# STM32P48.net
KiCad netlist of a schematic drawn in Altium Designer
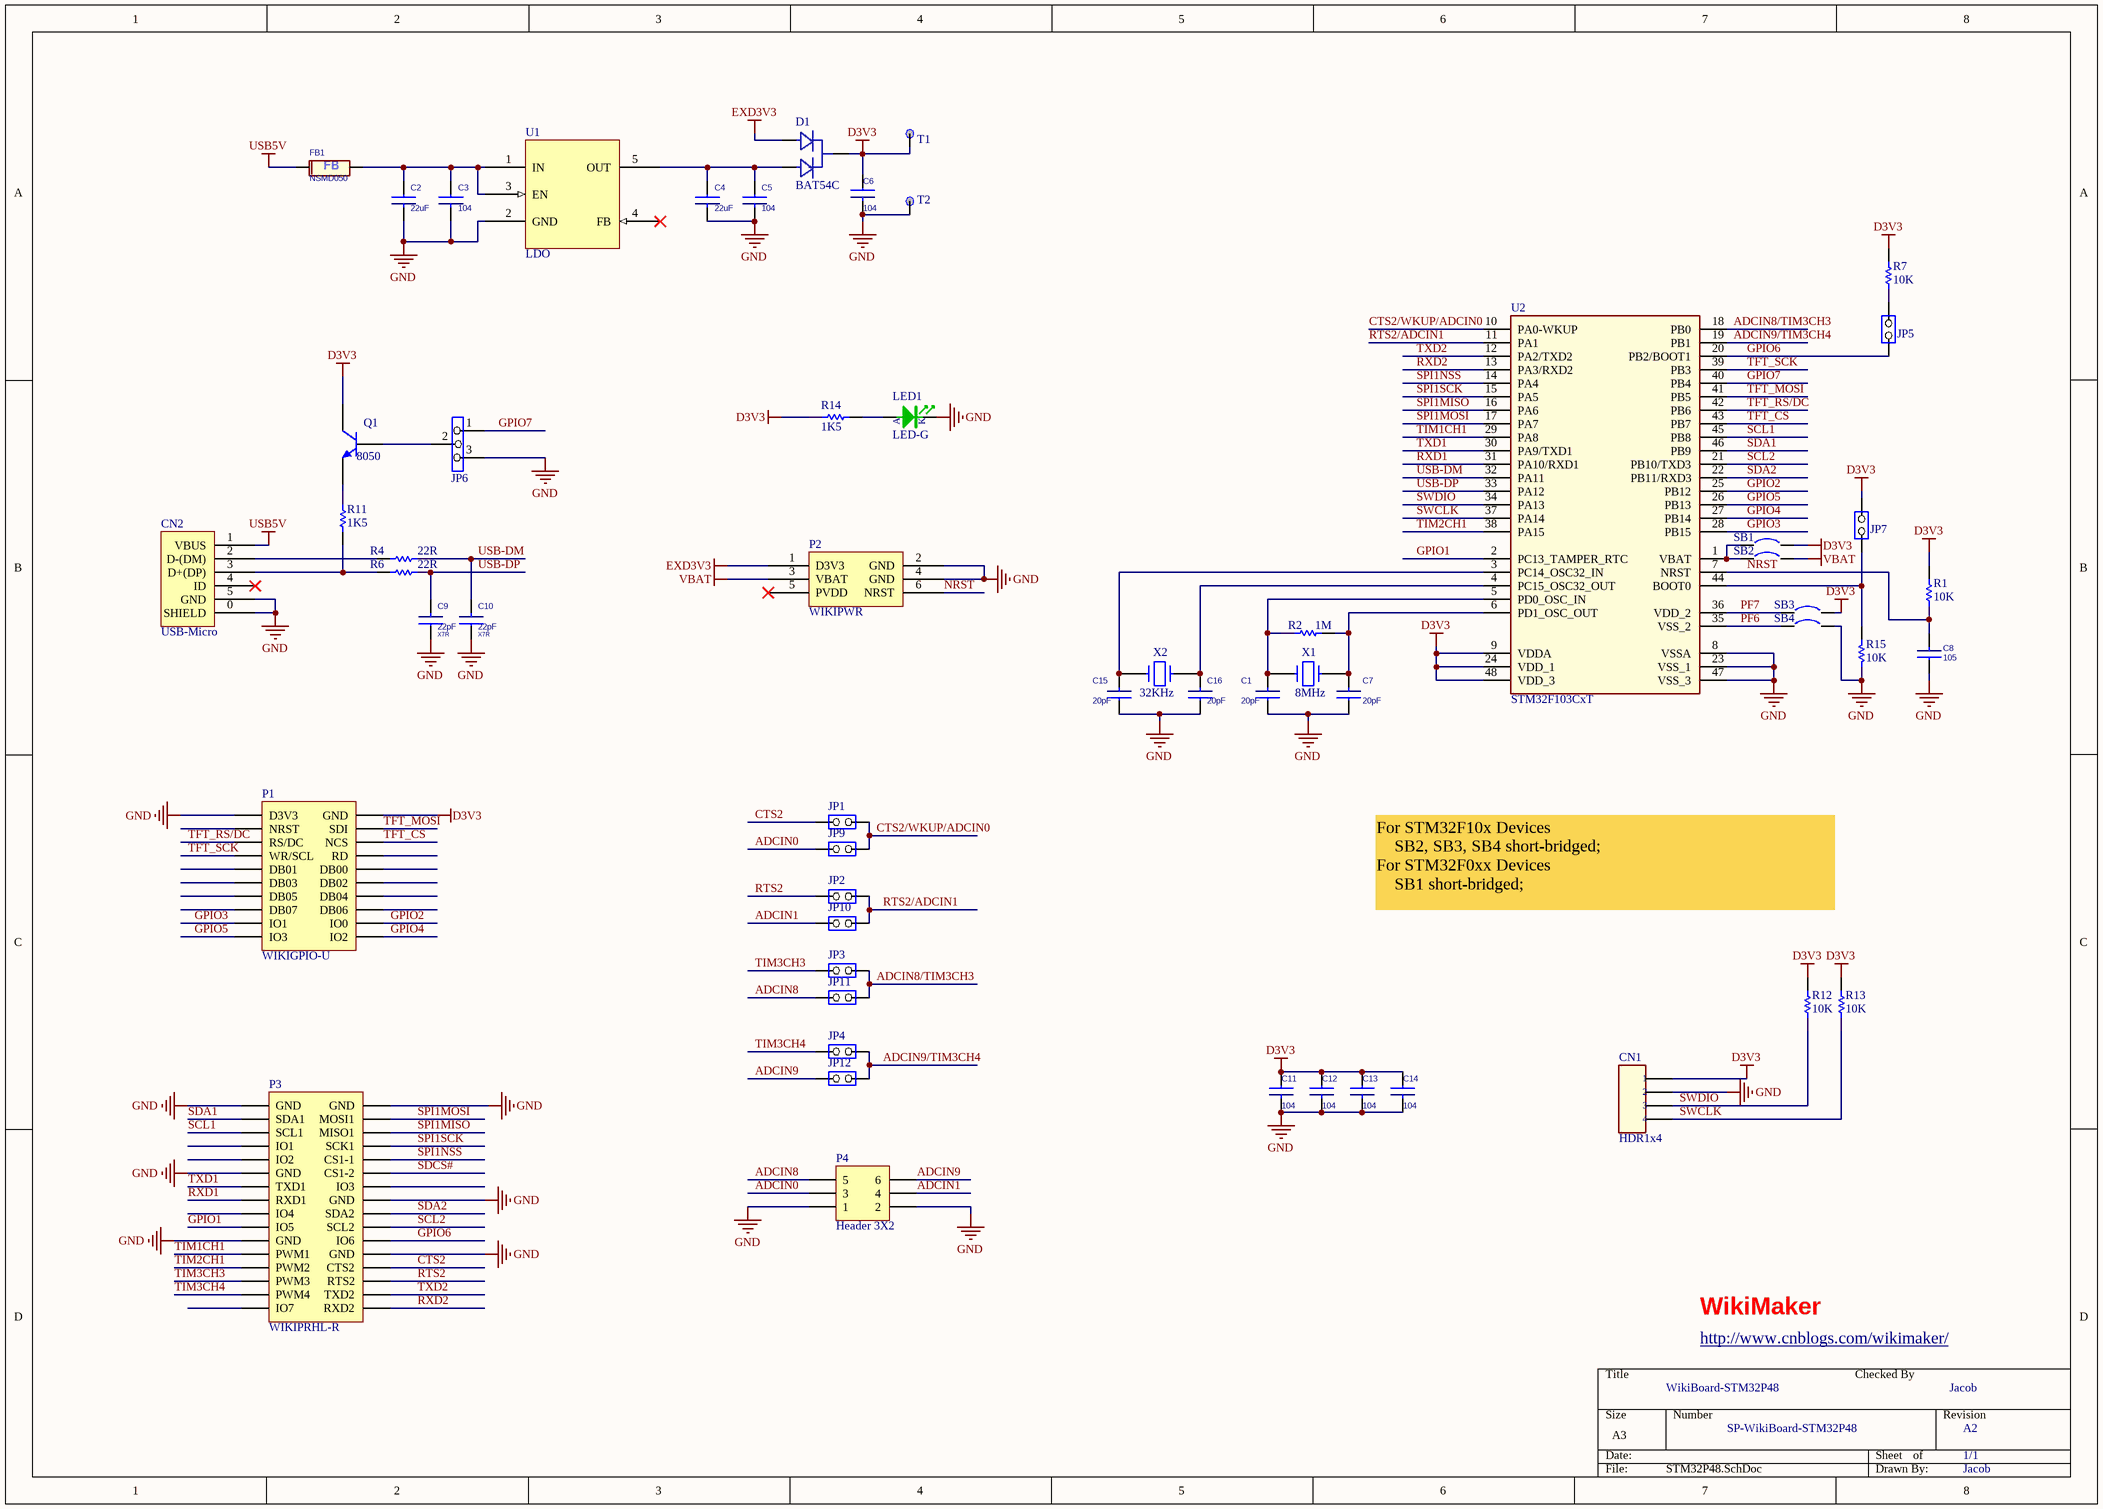
[diagram p0: STM32P48.SchDoc]

(export (version "E")
  (design (tool "Eeschema 10.0.6"))
  (components
    (comp (ref "C1")
      (value "20pF")
      (footprint "C0603")
      (fields (field (name "作者") "符观辉"))
      (libsource (lib "Mylib") (part "CAP"))
    )
    (comp (ref "C2") (value "22uF") (footprint "C0805") (libsource (lib "Mylib") (part "CAP")))
    (comp (ref "C3") (value "104") (footprint "C0603") (libsource (lib "Mylib") (part "CAP")))
    (comp (ref "C4") (value "22uF") (footprint "C0805") (libsource (lib "Mylib") (part "CAP")))
    (comp (ref "C5") (value "104") (footprint "C0603") (libsource (lib "Mylib") (part "CAP")))
    (comp (ref "C6") (value "104") (footprint "C0603") (libsource (lib "Mylib") (part "CAP")))
    (comp (ref "C7")
      (value "20pF")
      (footprint "C0603")
      (fields (field (name "作者") "符观辉"))
      (libsource (lib "Mylib") (part "CAP"))
    )
    (comp (ref "C8")
      (value "105")
      (footprint "C0603")
      (fields (field (name "作者") "符观辉"))
      (libsource (lib "Mylib") (part "CAP"))
    )
    (comp (ref "C9")
      (value "22pF")
      (footprint "C0603")
      (fields (field (name "ALTIUM_UNNAMED_1") "X7R") (field (name "作者") "符观辉"))
      (libsource (lib "Mylib") (part "CAP"))
    )
    (comp (ref "C10")
      (value "22pF")
      (footprint "C0603")
      (fields (field (name "ALTIUM_UNNAMED_1") "X7R") (field (name "作者") "符观辉"))
      (libsource (lib "Mylib") (part "CAP"))
    )
    (comp (ref "C11") (value "104") (footprint "C0603") (libsource (lib "Mylib") (part "CAP")))
    (comp (ref "C12") (value "104") (footprint "C0603") (libsource (lib "Mylib") (part "CAP")))
    (comp (ref "C13") (value "104") (footprint "C0603") (libsource (lib "Mylib") (part "CAP")))
    (comp (ref "C14") (value "104") (footprint "C0603") (libsource (lib "Mylib") (part "CAP")))
    (comp (ref "C15")
      (value "20pF")
      (footprint "C0603")
      (fields (field (name "作者") "符观辉"))
      (libsource (lib "Mylib") (part "CAP"))
    )
    (comp (ref "C16")
      (value "20pF")
      (footprint "C0603")
      (fields (field (name "作者") "符观辉"))
      (libsource (lib "Mylib") (part "CAP"))
    )
    (comp (ref "CN1") (value "HDR1x4") (footprint "HDR1x4") (libsource (lib "Mylib") (part "CON4")))
    (comp (ref "CN2")
      (value "USB-Micro")
      (footprint "USB-MICRO-Lite")
      (libsource (lib "Connector") (part "USB-Micro"))
    )
    (comp (ref "D1")
      (value "BAT54C")
      (footprint "BAT54C")
      (description "DOUBLE SHOTTKEY DIODES")
      (libsource (lib "Misc") (part "BAT54C"))
    )
    (comp (ref "FB1")
      (value "NSMD050")
      (footprint "R1206")
      (description "Ferrite Beads Inductors Impedance:120Ω±25% Rated Current:1500mA DC Resistance:0.095Ω")
      (fields
        (field (name "MANUFACTURER") "muRata")
        (field (name "MANUFACTURER PART NUMBER") "BLM15EG121SN1")
      )
      (libsource (lib "Mylib") (part "FB"))
    )
    (comp (ref "JP1")
      (value "Jumper2-2")
      (footprint "HDR1X2/2.00MM")
      (description "Jumper2")
      (libsource (lib "Misc") (part "Jumper2-2"))
    )
    (comp (ref "JP2")
      (value "Jumper2-2")
      (footprint "HDR1X2/2.00MM")
      (description "Jumper2")
      (libsource (lib "Misc") (part "Jumper2-2"))
    )
    (comp (ref "JP3")
      (value "Jumper2-2")
      (footprint "HDR1X2/2.00MM")
      (description "Jumper2")
      (libsource (lib "Misc") (part "Jumper2-2"))
    )
    (comp (ref "JP4")
      (value "Jumper2-2")
      (footprint "HDR1X2/2.00MM")
      (description "Jumper2")
      (libsource (lib "Misc") (part "Jumper2-2"))
    )
    (comp (ref "JP5")
      (value "Jumper2-2")
      (footprint "HDR1X2/2.00MM")
      (description "Jumper2")
      (libsource (lib "Misc") (part "Jumper2-2"))
    )
    (comp (ref "JP6") (value "Jumper3") (footprint "HDR1X3/2.00mm") (libsource (lib "Misc") (part "Jumper3")))
    (comp (ref "JP7")
      (value "Jumper2-2")
      (footprint "HDR1X2/2.00MM")
      (description "Jumper2")
      (libsource (lib "Misc") (part "Jumper2-2"))
    )
    (comp (ref "JP9")
      (value "Jumper2-2")
      (footprint "HDR1X2/2.00MM")
      (description "Jumper2")
      (libsource (lib "Misc") (part "Jumper2-2"))
    )
    (comp (ref "JP10")
      (value "Jumper2-2")
      (footprint "HDR1X2/2.00MM")
      (description "Jumper2")
      (libsource (lib "Misc") (part "Jumper2-2"))
    )
    (comp (ref "JP11")
      (value "Jumper2-2")
      (footprint "HDR1X2/2.00MM")
      (description "Jumper2")
      (libsource (lib "Misc") (part "Jumper2-2"))
    )
    (comp (ref "JP12")
      (value "Jumper2-2")
      (footprint "HDR1X2/2.00MM")
      (description "Jumper2")
      (libsource (lib "Misc") (part "Jumper2-2"))
    )
    (comp (ref "LED1") (value "LED-G") (footprint "D0805") (libsource (lib "Mylib") (part "LED-G")))
    (comp (ref "P1")
      (value "WIKIGPIO-U")
      (footprint "HDR2X10/2.54MM-WIKIGPIO-U")
      (description "Header, 9-Pin, Dual row")
      (fields (field (name "PUBLISHER") "Altium Limited"))
      (libsource (lib "Connector") (part "WIKIGPIO-U"))
    )
    (comp (ref "P2")
      (value "WIKIPWR")
      (footprint "WIKIPWR")
      (description "PWR HDR")
      (libsource (lib "Connector") (part "WIKIPWR"))
    )
    (comp (ref "P3")
      (value "WIKIPRHL-R")
      (footprint "HDR2X16-WIKIPRHL-R")
      (description "Header, 16-Pin, Dual row")
      (fields (field (name "PUBLISHER") "Altium Limited"))
      (libsource (lib "Connector") (part "WIKIPRHL-R"))
    )
    (comp (ref "P4")
      (value "Header 3X2")
      (footprint "HDR2X3/2.54MM")
      (description "Header, 3-Pin, Dual row")
      (fields (field (name "PUBLISHER") "Altium Limited"))
      (libsource (lib "Miscellaneous Connectors") (part "Header 3X2"))
    )
    (comp (ref "Q1")
      (value "8050")
      (footprint "SOT23-3L(123)")
      (description "NPN General Purpose Amplifier")
      (fields (field (name "PUBLISHER") "Altium Limited"))
      (libsource (lib "Misc") (part "8050"))
    )
    (comp (ref "R1")
      (value "10K")
      (footprint "R0603")
      (description "Resistor")
      (libsource (lib "Mylib") (part "RES"))
    )
    (comp (ref "R2")
      (value "1M")
      (footprint "R0603")
      (description "Resistor")
      (libsource (lib "Mylib") (part "RES"))
    )
    (comp (ref "R4")
      (value "22R")
      (footprint "R0603")
      (description "Resistor")
      (libsource (lib "Mylib") (part "RES"))
    )
    (comp (ref "R6")
      (value "22R")
      (footprint "R0603")
      (description "Resistor")
      (libsource (lib "Mylib") (part "RES"))
    )
    (comp (ref "R7")
      (value "10K")
      (footprint "R0603")
      (description "Resistor")
      (libsource (lib "Mylib") (part "RES"))
    )
    (comp (ref "R11")
      (value "1K5")
      (footprint "R0603")
      (description "Resistor")
      (libsource (lib "Mylib") (part "RES"))
    )
    (comp (ref "R12")
      (value "10K")
      (footprint "R0603")
      (description "Resistor")
      (libsource (lib "Mylib") (part "RES"))
    )
    (comp (ref "R13")
      (value "10K")
      (footprint "R0603")
      (description "Resistor")
      (libsource (lib "Mylib") (part "RES"))
    )
    (comp (ref "R14")
      (value "1K5")
      (footprint "R0603")
      (description "Resistor")
      (libsource (lib "Mylib") (part "RES"))
    )
    (comp (ref "R15")
      (value "10K")
      (footprint "R0603")
      (description "Resistor")
      (libsource (lib "Mylib") (part "RES"))
    )
    (comp (ref "SB1")
      (value "Circuit Breaker")
      (footprint "JP2_SMD")
      (fields (field (name "PUBLISHER") "Altium Limited"))
      (libsource (lib "MB915") (part "Circuit Breaker"))
    )
    (comp (ref "SB2")
      (value "Circuit Breaker")
      (footprint "JP2_SMD")
      (fields (field (name "PUBLISHER") "Altium Limited"))
      (libsource (lib "MB915") (part "Circuit Breaker"))
    )
    (comp (ref "SB3")
      (value "Circuit Breaker")
      (footprint "JP2_SMD")
      (fields (field (name "PUBLISHER") "Altium Limited"))
      (libsource (lib "MB915") (part "Circuit Breaker"))
    )
    (comp (ref "SB4")
      (value "Circuit Breaker")
      (footprint "JP2_SMD")
      (fields (field (name "PUBLISHER") "Altium Limited"))
      (libsource (lib "MB915") (part "Circuit Breaker"))
    )
    (comp (ref "T1")
      (value "TP")
      (footprint "TP")
      (description "Test Point")
      (libsource (lib "Misc") (part "TP"))
    )
    (comp (ref "T2")
      (value "TP")
      (footprint "TP")
      (description "Test Point")
      (libsource (lib "Misc") (part "TP"))
    )
    (comp (ref "U1")
      (value "LDO")
      (footprint "SOT23-5")
      (description "General LDO SOT23-5")
      (libsource (lib "Power") (part "LDO-SOT23-5"))
    )
    (comp (ref "U2")
      (value "STM32F103CxT")
      (footprint "LQFP-48")
      (description "Cortex M3, 48-pin LQFP")
      (libsource (lib "Processor") (part "STM32F103CxT"))
    )
    (comp (ref "X1")
      (value "8MHz")
      (footprint "XTAL_socket")
      (description "Crystal")
      (libsource (lib "*") (part "CRYSTAL"))
    )
    (comp (ref "X2")
      (value "32KHz")
      (footprint "XTAL0602")
      (description "Crystal")
      (libsource (lib "*") (part "CRYSTAL"))
    )
  )
  (nets
    (net (code "1") (name "/ADCIN0") (class "Default")
      (node (ref "JP9") (pin "1") (pinfunction "COMMON_1") (pintype "passive"))
      (node (ref "P4") (pin "3") (pinfunction "3_3") (pintype "passive"))
    )
    (net (code "2") (name "/ADCIN1") (class "Default")
      (node (ref "JP10") (pin "1") (pinfunction "COMMON_1") (pintype "passive"))
      (node (ref "P4") (pin "4") (pinfunction "4_4") (pintype "passive"))
    )
    (net (code "3") (name "/ADCIN8") (class "Default")
      (node (ref "JP11") (pin "1") (pinfunction "COMMON_1") (pintype "passive"))
      (node (ref "P4") (pin "5") (pinfunction "5_5") (pintype "passive"))
    )
    (net (code "4") (name "/ADCIN8{slash}TIM3CH3") (class "Default")
      (node (ref "JP11") (pin "2") (pinfunction "NO_2") (pintype "passive"))
      (node (ref "JP3") (pin "2") (pinfunction "NO_2") (pintype "passive"))
      (node (ref "U2") (pin "18") (pinfunction "PB0_18") (pintype "passive"))
    )
    (net (code "5") (name "/ADCIN9") (class "Default")
      (node (ref "JP12") (pin "1") (pinfunction "COMMON_1") (pintype "passive"))
      (node (ref "P4") (pin "6") (pinfunction "6_6") (pintype "passive"))
    )
    (net (code "6") (name "/ADCIN9{slash}TIM3CH4") (class "Default")
      (node (ref "JP12") (pin "2") (pinfunction "NO_2") (pintype "passive"))
      (node (ref "JP4") (pin "2") (pinfunction "NO_2") (pintype "passive"))
      (node (ref "U2") (pin "19") (pinfunction "PB1_19") (pintype "passive"))
    )
    (net (code "7") (name "/CTS2") (class "Default")
      (node (ref "JP1") (pin "1") (pinfunction "COMMON_1") (pintype "passive"))
      (node (ref "P3") (pin "26") (pinfunction "CTS2_26") (pintype "passive"))
    )
    (net (code "8") (name "/CTS2{slash}WKUP{slash}ADCIN0") (class "Default")
      (node (ref "JP1") (pin "2") (pinfunction "NO_2") (pintype "passive"))
      (node (ref "JP9") (pin "2") (pinfunction "NO_2") (pintype "passive"))
      (node (ref "U2") (pin "10") (pinfunction "PA0-WKUP_10") (pintype "passive"))
    )
    (net (code "9") (name "/GPIO1") (class "Default")
      (node (ref "P3") (pin "19") (pinfunction "IO5_19") (pintype "passive"))
      (node (ref "U2") (pin "2") (pinfunction "PC13_TAMPER_RTC_2") (pintype "passive"))
    )
    (net (code "10") (name "/GPIO2") (class "Default")
      (node (ref "P1") (pin "17") (pinfunction "IO0_17") (pintype "passive"))
      (node (ref "U2") (pin "25") (pinfunction "PB12_25") (pintype "passive"))
    )
    (net (code "11") (name "/GPIO3") (class "Default")
      (node (ref "P1") (pin "18") (pinfunction "IO1_18") (pintype "passive"))
      (node (ref "U2") (pin "28") (pinfunction "PB15_28") (pintype "passive"))
    )
    (net (code "12") (name "/GPIO4") (class "Default")
      (node (ref "P1") (pin "19") (pinfunction "IO2_19") (pintype "passive"))
      (node (ref "U2") (pin "27") (pinfunction "PB14_27") (pintype "passive"))
    )
    (net (code "13") (name "/GPIO5") (class "Default")
      (node (ref "P1") (pin "20") (pinfunction "IO3_20") (pintype "passive"))
      (node (ref "U2") (pin "26") (pinfunction "PB13_26") (pintype "passive"))
    )
    (net (code "14") (name "/GPIO6") (class "Default")
      (node (ref "JP5") (pin "1") (pinfunction "COMMON_1") (pintype "passive"))
      (node (ref "P3") (pin "22") (pinfunction "IO6_22") (pintype "passive"))
      (node (ref "U2") (pin "20") (pinfunction "PB2/BOOT1_20") (pintype "passive"))
    )
    (net (code "15") (name "/GPIO7") (class "Default")
      (node (ref "JP6") (pin "1") (pintype "passive"))
      (node (ref "U2") (pin "40") (pinfunction "PB4_40") (pintype "passive"))
    )
    (net (code "16") (name "/NRST") (class "Default")
      (node (ref "C8") (pin "1") (pinfunction "1_1") (pintype "passive"))
      (node (ref "P2") (pin "6") (pinfunction "NRST_6") (pintype "passive"))
      (node (ref "R1") (pin "1") (pinfunction "1_1") (pintype "passive"))
      (node (ref "U2") (pin "7") (pinfunction "NRST_7") (pintype "passive"))
    )
    (net (code "17") (name "/PF6") (class "Default")
      (node (ref "SB4") (pin "1") (pinfunction "1_1") (pintype "passive"))
      (node (ref "U2") (pin "35") (pinfunction "VSS_2_35") (pintype "passive"))
    )
    (net (code "18") (name "/PF7") (class "Default")
      (node (ref "SB3") (pin "1") (pinfunction "1_1") (pintype "passive"))
      (node (ref "U2") (pin "36") (pinfunction "VDD_2_36") (pintype "passive"))
    )
    (net (code "19") (name "/RTS2") (class "Default")
      (node (ref "JP2") (pin "1") (pinfunction "COMMON_1") (pintype "passive"))
      (node (ref "P3") (pin "28") (pinfunction "RTS2_28") (pintype "passive"))
    )
    (net (code "20") (name "/RTS2{slash}ADCIN1") (class "Default")
      (node (ref "JP10") (pin "2") (pinfunction "NO_2") (pintype "passive"))
      (node (ref "JP2") (pin "2") (pinfunction "NO_2") (pintype "passive"))
      (node (ref "U2") (pin "11") (pinfunction "PA1_11") (pintype "passive"))
    )
    (net (code "21") (name "/RXD1") (class "Default")
      (node (ref "P3") (pin "15") (pinfunction "RXD1_15") (pintype "passive"))
      (node (ref "U2") (pin "31") (pinfunction "PA10/RXD1_31") (pintype "passive"))
    )
    (net (code "22") (name "/RXD2") (class "Default")
      (node (ref "P3") (pin "32") (pinfunction "RXD2_32") (pintype "passive"))
      (node (ref "U2") (pin "13") (pinfunction "PA3/RXD2_13") (pintype "passive"))
    )
    (net (code "23") (name "/SCL1") (class "Default")
      (node (ref "P3") (pin "5") (pinfunction "SCL1_5") (pintype "passive"))
      (node (ref "U2") (pin "45") (pinfunction "PB8_45") (pintype "passive"))
    )
    (net (code "24") (name "/SCL2") (class "Default")
      (node (ref "P3") (pin "20") (pinfunction "SCL2_20") (pintype "passive"))
      (node (ref "U2") (pin "21") (pinfunction "PB10/TXD3_21") (pintype "passive"))
    )
    (net (code "25") (name "/SDA1") (class "Default")
      (node (ref "P3") (pin "3") (pinfunction "SDA1_3") (pintype "passive"))
      (node (ref "U2") (pin "46") (pinfunction "PB9_46") (pintype "passive"))
    )
    (net (code "26") (name "/SDA2") (class "Default")
      (node (ref "P3") (pin "18") (pinfunction "SDA2_18") (pintype "passive"))
      (node (ref "U2") (pin "22") (pinfunction "PB11/RXD3_22") (pintype "passive"))
    )
    (net (code "27") (name "/SDCS#") (class "Default")
      (node (ref "P3") (pin "12") (pinfunction "CS1-2_12") (pintype "passive"))
    )
    (net (code "28") (name "/SPI1MISO") (class "Default")
      (node (ref "P3") (pin "6") (pinfunction "MISO1_6") (pintype "passive"))
      (node (ref "U2") (pin "16") (pinfunction "PA6_16") (pintype "passive"))
    )
    (net (code "29") (name "/SPI1MOSI") (class "Default")
      (node (ref "P3") (pin "4") (pinfunction "MOSI1_4") (pintype "passive"))
      (node (ref "U2") (pin "17") (pinfunction "PA7_17") (pintype "passive"))
    )
    (net (code "30") (name "/SPI1NSS") (class "Default")
      (node (ref "P3") (pin "10") (pinfunction "CS1-1_10") (pintype "passive"))
      (node (ref "U2") (pin "14") (pinfunction "PA4_14") (pintype "passive"))
    )
    (net (code "31") (name "/SPI1SCK") (class "Default")
      (node (ref "P3") (pin "8") (pinfunction "SCK1_8") (pintype "passive"))
      (node (ref "U2") (pin "15") (pinfunction "PA5_15") (pintype "passive"))
    )
    (net (code "32") (name "/SWCLK") (class "Default")
      (node (ref "CN1") (pin "4") (pinfunction "4_4") (pintype "passive"))
      (node (ref "R13") (pin "1") (pinfunction "1_1") (pintype "passive"))
      (node (ref "U2") (pin "37") (pinfunction "PA14_37") (pintype "passive"))
    )
    (net (code "33") (name "/SWDIO") (class "Default")
      (node (ref "CN1") (pin "3") (pinfunction "3_3") (pintype "passive"))
      (node (ref "R12") (pin "1") (pinfunction "1_1") (pintype "passive"))
      (node (ref "U2") (pin "34") (pinfunction "PA13_34") (pintype "passive"))
    )
    (net (code "34") (name "/TFT_CS") (class "Default")
      (node (ref "P1") (pin "5") (pinfunction "NCS_5") (pintype "passive"))
      (node (ref "U2") (pin "43") (pinfunction "PB7_43") (pintype "passive"))
    )
    (net (code "35") (name "/TFT_MOSI") (class "Default")
      (node (ref "P1") (pin "3") (pinfunction "SDI_3") (pintype "passive"))
      (node (ref "U2") (pin "41") (pinfunction "PB5_41") (pintype "passive"))
    )
    (net (code "36") (name "/TFT_RS{slash}DC") (class "Default")
      (node (ref "P1") (pin "6") (pinfunction "RS/DC_6") (pintype "passive"))
      (node (ref "U2") (pin "42") (pinfunction "PB6_42") (pintype "passive"))
    )
    (net (code "37") (name "/TFT_SCK") (class "Default")
      (node (ref "P1") (pin "8") (pinfunction "WR/SCL_8") (pintype "passive"))
      (node (ref "U2") (pin "39") (pinfunction "PB3_39") (pintype "passive"))
    )
    (net (code "38") (name "/TIM1CH1") (class "Default")
      (node (ref "P3") (pin "23") (pinfunction "PWM1_23") (pintype "passive"))
      (node (ref "U2") (pin "29") (pinfunction "PA8_29") (pintype "passive"))
    )
    (net (code "39") (name "/TIM2CH1") (class "Default")
      (node (ref "P3") (pin "25") (pinfunction "PWM2_25") (pintype "passive"))
      (node (ref "U2") (pin "38") (pinfunction "PA15_38") (pintype "passive"))
    )
    (net (code "40") (name "/TIM3CH3") (class "Default")
      (node (ref "JP3") (pin "1") (pinfunction "COMMON_1") (pintype "passive"))
      (node (ref "P3") (pin "27") (pinfunction "PWM3_27") (pintype "passive"))
    )
    (net (code "41") (name "/TIM3CH4") (class "Default")
      (node (ref "JP4") (pin "1") (pinfunction "COMMON_1") (pintype "passive"))
      (node (ref "P3") (pin "29") (pinfunction "PWM4_29") (pintype "passive"))
    )
    (net (code "42") (name "/TXD1") (class "Default")
      (node (ref "P3") (pin "13") (pinfunction "TXD1_13") (pintype "passive"))
      (node (ref "U2") (pin "30") (pinfunction "PA9/TXD1_30") (pintype "passive"))
    )
    (net (code "43") (name "/TXD2") (class "Default")
      (node (ref "P3") (pin "30") (pinfunction "TXD2_30") (pintype "passive"))
      (node (ref "U2") (pin "12") (pinfunction "PA2/TXD2_12") (pintype "passive"))
    )
    (net (code "44") (name "/USB-DM") (class "Default")
      (node (ref "C10") (pin "1") (pinfunction "1_1") (pintype "passive"))
      (node (ref "R4") (pin "1") (pinfunction "1_1") (pintype "passive"))
      (node (ref "U2") (pin "32") (pinfunction "PA11_32") (pintype "passive"))
    )
    (net (code "45") (name "/USB-DP") (class "Default")
      (node (ref "C9") (pin "1") (pinfunction "1_1") (pintype "passive"))
      (node (ref "R6") (pin "1") (pinfunction "1_1") (pintype "passive"))
      (node (ref "U2") (pin "33") (pinfunction "PA12_33") (pintype "passive"))
    )
    (net (code "46") (name "D3V3") (class "Default")
      (node (ref "C11") (pin "2") (pinfunction "2_2") (pintype "passive"))
      (node (ref "C12") (pin "2") (pinfunction "2_2") (pintype "passive"))
      (node (ref "C13") (pin "2") (pinfunction "2_2") (pintype "passive"))
      (node (ref "C14") (pin "2") (pinfunction "2_2") (pintype "passive"))
      (node (ref "C6") (pin "2") (pinfunction "2_2") (pintype "passive"))
      (node (ref "CN1") (pin "1") (pinfunction "1_1") (pintype "passive"))
      (node (ref "D1") (pin "3") (pinfunction "3_3") (pintype "passive"))
      (node (ref "JP7") (pin "2") (pinfunction "NO_2") (pintype "passive"))
      (node (ref "P1") (pin "1") (pinfunction "GND_1") (pintype "passive"))
      (node (ref "Q1") (pin "3") (pinfunction "C_3") (pintype "passive"))
      (node (ref "R1") (pin "2") (pinfunction "2_2") (pintype "passive"))
      (node (ref "R12") (pin "2") (pinfunction "2_2") (pintype "passive"))
      (node (ref "R13") (pin "2") (pinfunction "2_2") (pintype "passive"))
      (node (ref "R14") (pin "1") (pinfunction "1_1") (pintype "passive"))
      (node (ref "R7") (pin "2") (pinfunction "2_2") (pintype "passive"))
      (node (ref "SB1") (pin "2") (pinfunction "2_2") (pintype "passive"))
      (node (ref "SB3") (pin "2") (pinfunction "2_2") (pintype "passive"))
      (node (ref "T1") (pin "1") (pinfunction "1_1") (pintype "passive"))
      (node (ref "U2") (pin "24") (pinfunction "VDD_1_24") (pintype "passive"))
      (node (ref "U2") (pin "48") (pinfunction "VDD_3_48") (pintype "passive"))
      (node (ref "U2") (pin "9") (pinfunction "VDDA_9") (pintype "passive"))
    )
    (net (code "47") (name "EXD3V3") (class "Default")
      (node (ref "D1") (pin "2") (pintype "passive"))
      (node (ref "P2") (pin "1") (pinfunction "D3V3_1") (pintype "passive"))
    )
    (net (code "48") (name "GND") (class "Default")
      (node (ref "C1") (pin "2") (pinfunction "2_2") (pintype "passive"))
      (node (ref "C10") (pin "2") (pinfunction "2_2") (pintype "passive"))
      (node (ref "C11") (pin "1") (pinfunction "1_1") (pintype "passive"))
      (node (ref "C12") (pin "1") (pinfunction "1_1") (pintype "passive"))
      (node (ref "C13") (pin "1") (pinfunction "1_1") (pintype "passive"))
      (node (ref "C14") (pin "1") (pinfunction "1_1") (pintype "passive"))
      (node (ref "C15") (pin "2") (pinfunction "2_2") (pintype "passive"))
      (node (ref "C16") (pin "2") (pinfunction "2_2") (pintype "passive"))
      (node (ref "C2") (pin "1") (pinfunction "1_1") (pintype "passive"))
      (node (ref "C3") (pin "1") (pinfunction "1_1") (pintype "passive"))
      (node (ref "C4") (pin "1") (pinfunction "1_1") (pintype "passive"))
      (node (ref "C5") (pin "1") (pinfunction "1_1") (pintype "passive"))
      (node (ref "C6") (pin "1") (pinfunction "1_1") (pintype "passive"))
      (node (ref "C7") (pin "2") (pinfunction "2_2") (pintype "passive"))
      (node (ref "C8") (pin "2") (pinfunction "2_2") (pintype "passive"))
      (node (ref "C9") (pin "2") (pinfunction "2_2") (pintype "passive"))
      (node (ref "CN1") (pin "2") (pinfunction "2_2") (pintype "passive"))
      (node (ref "CN2") (pin "0") (pinfunction "SHIELD_0") (pintype "passive"))
      (node (ref "CN2") (pin "5") (pinfunction "GND_5") (pintype "passive"))
      (node (ref "JP6") (pin "3") (pintype "passive"))
      (node (ref "LED1") (pin "K") (pinfunction "2_K") (pintype "passive"))
      (node (ref "P1") (pin "2") (pinfunction "D3V3_2") (pintype "passive"))
      (node (ref "P2") (pin "2") (pinfunction "GND_2") (pintype "passive"))
      (node (ref "P2") (pin "4") (pinfunction "GND_4") (pintype "passive"))
      (node (ref "P3") (pin "1") (pinfunction "GND_1") (pintype "passive"))
      (node (ref "P3") (pin "11") (pinfunction "GND_11") (pintype "passive"))
      (node (ref "P3") (pin "16") (pinfunction "GND_16") (pintype "passive"))
      (node (ref "P3") (pin "2") (pinfunction "GND_2") (pintype "passive"))
      (node (ref "P3") (pin "21") (pinfunction "GND_21") (pintype "passive"))
      (node (ref "P3") (pin "24") (pinfunction "GND_24") (pintype "passive"))
      (node (ref "P4") (pin "1") (pinfunction "1_1") (pintype "passive"))
      (node (ref "P4") (pin "2") (pinfunction "2_2") (pintype "passive"))
      (node (ref "R15") (pin "1") (pinfunction "1_1") (pintype "passive"))
      (node (ref "SB4") (pin "2") (pinfunction "2_2") (pintype "passive"))
      (node (ref "T2") (pin "1") (pinfunction "1_1") (pintype "passive"))
      (node (ref "U1") (pin "2") (pinfunction "GND_2") (pintype "power_in"))
      (node (ref "U2") (pin "23") (pinfunction "VSS_1_23") (pintype "passive"))
      (node (ref "U2") (pin "47") (pinfunction "VSS_3_47") (pintype "passive"))
      (node (ref "U2") (pin "8") (pinfunction "VSSA_8") (pintype "passive"))
    )
    (net (code "49") (name "Net-(CN2-D+(DP))") (class "Default")
      (node (ref "CN2") (pin "3") (pinfunction "D+(DP)_3") (pintype "passive"))
      (node (ref "R11") (pin "2") (pinfunction "2_2") (pintype "passive"))
      (node (ref "R6") (pin "2") (pinfunction "2_2") (pintype "passive"))
    )
    (net (code "50") (name "Net-(CN2-D-(DM))") (class "Default")
      (node (ref "CN2") (pin "2") (pinfunction "D-(DM)_2") (pintype "passive"))
      (node (ref "R4") (pin "2") (pinfunction "2_2") (pintype "passive"))
    )
    (net (code "51") (name "Net-(JP5-NO)") (class "Default")
      (node (ref "JP5") (pin "2") (pinfunction "NO_2") (pintype "passive"))
      (node (ref "R7") (pin "1") (pinfunction "1_1") (pintype "passive"))
    )
    (net (code "52") (name "Net-(JP7-COMMON)") (class "Default")
      (node (ref "JP7") (pin "1") (pinfunction "COMMON_1") (pintype "passive"))
      (node (ref "R15") (pin "2") (pinfunction "2_2") (pintype "passive"))
      (node (ref "U2") (pin "44") (pinfunction "BOOT0_44") (pintype "passive"))
    )
    (net (code "53") (name "Net-(LED1-1)") (class "Default")
      (node (ref "LED1") (pin "A") (pinfunction "1_A") (pintype "passive"))
      (node (ref "R14") (pin "2") (pinfunction "2_2") (pintype "passive"))
    )
    (net (code "54") (name "Net-(Q1-B)") (class "Default")
      (node (ref "JP6") (pin "2") (pintype "passive"))
      (node (ref "Q1") (pin "1") (pinfunction "B_1") (pintype "passive"))
    )
    (net (code "55") (name "Net-(Q1-E)") (class "Default")
      (node (ref "Q1") (pin "2") (pinfunction "E_2") (pintype "passive"))
      (node (ref "R11") (pin "1") (pinfunction "1_1") (pintype "passive"))
    )
    (net (code "56") (name "Net-(U1-EN)") (class "Default")
      (node (ref "C2") (pin "2") (pinfunction "2_2") (pintype "passive"))
      (node (ref "C3") (pin "2") (pinfunction "2_2") (pintype "passive"))
      (node (ref "FB1") (pin "2") (pinfunction "2_2") (pintype "passive"))
      (node (ref "U1") (pin "1") (pinfunction "IN_1") (pintype "power_in"))
      (node (ref "U1") (pin "3") (pinfunction "EN_3") (pintype "input"))
    )
    (net (code "57") (name "Net-(U1-OUT)") (class "Default")
      (node (ref "C4") (pin "2") (pinfunction "2_2") (pintype "passive"))
      (node (ref "C5") (pin "2") (pinfunction "2_2") (pintype "passive"))
      (node (ref "D1") (pin "1") (pintype "passive"))
      (node (ref "U1") (pin "5") (pinfunction "OUT_5") (pintype "power_in"))
    )
    (net (code "58") (name "Net-(U2-PC14_OSC32_IN)") (class "Default")
      (node (ref "C15") (pin "1") (pinfunction "1_1") (pintype "passive"))
      (node (ref "U2") (pin "3") (pinfunction "PC14_OSC32_IN_3") (pintype "passive"))
      (node (ref "X2") (pin "2") (pinfunction "2_2") (pintype "passive"))
    )
    (net (code "59") (name "Net-(U2-PC15_OSC32_OUT)") (class "Default")
      (node (ref "C16") (pin "1") (pinfunction "1_1") (pintype "passive"))
      (node (ref "U2") (pin "4") (pinfunction "PC15_OSC32_OUT_4") (pintype "passive"))
      (node (ref "X2") (pin "1") (pinfunction "1_1") (pintype "passive"))
    )
    (net (code "60") (name "Net-(U2-PD0_OSC_IN)") (class "Default")
      (node (ref "C1") (pin "1") (pinfunction "1_1") (pintype "passive"))
      (node (ref "R2") (pin "1") (pinfunction "1_1") (pintype "passive"))
      (node (ref "U2") (pin "5") (pinfunction "PD0_OSC_IN_5") (pintype "passive"))
      (node (ref "X1") (pin "2") (pinfunction "2_2") (pintype "passive"))
    )
    (net (code "61") (name "Net-(U2-PD1_OSC_OUT)") (class "Default")
      (node (ref "C7") (pin "1") (pinfunction "1_1") (pintype "passive"))
      (node (ref "R2") (pin "2") (pinfunction "2_2") (pintype "passive"))
      (node (ref "U2") (pin "6") (pinfunction "PD1_OSC_OUT_6") (pintype "passive"))
      (node (ref "X1") (pin "1") (pinfunction "1_1") (pintype "passive"))
    )
    (net (code "62") (name "Net-(U2-VBAT)") (class "Default")
      (node (ref "SB1") (pin "1") (pinfunction "1_1") (pintype "passive"))
      (node (ref "SB2") (pin "1") (pinfunction "1_1") (pintype "passive"))
      (node (ref "U2") (pin "1") (pinfunction "VBAT_1") (pintype "passive"))
    )
    (net (code "63") (name "USB5V") (class "Default")
      (node (ref "CN2") (pin "1") (pinfunction "VBUS_1") (pintype "passive"))
      (node (ref "FB1") (pin "1") (pinfunction "1_1") (pintype "passive"))
    )
    (net (code "64") (name "VBAT") (class "Default")
      (node (ref "P2") (pin "3") (pinfunction "VBAT_3") (pintype "passive"))
      (node (ref "SB2") (pin "2") (pinfunction "2_2") (pintype "passive"))
    )
    (net (code "65") (name "unconnected-(CN2-ID-Pad4)") (class "Default")
      (node (ref "CN2") (pin "4") (pinfunction "ID_4") (pintype "passive+no_connect"))
    )
    (net (code "66") (name "unconnected-(P1-DB00-Pad9)") (class "Default")
      (node (ref "P1") (pin "9") (pinfunction "DB00_9") (pintype "passive"))
    )
    (net (code "67") (name "unconnected-(P1-DB01-Pad10)") (class "Default")
      (node (ref "P1") (pin "10") (pinfunction "DB01_10") (pintype "passive"))
    )
    (net (code "68") (name "unconnected-(P1-DB02-Pad11)") (class "Default")
      (node (ref "P1") (pin "11") (pinfunction "DB02_11") (pintype "passive"))
    )
    (net (code "69") (name "unconnected-(P1-DB03-Pad12)") (class "Default")
      (node (ref "P1") (pin "12") (pinfunction "DB03_12") (pintype "passive"))
    )
    (net (code "70") (name "unconnected-(P1-DB04-Pad13)") (class "Default")
      (node (ref "P1") (pin "13") (pinfunction "DB04_13") (pintype "passive"))
    )
    (net (code "71") (name "unconnected-(P1-DB05-Pad14)") (class "Default")
      (node (ref "P1") (pin "14") (pinfunction "DB05_14") (pintype "passive"))
    )
    (net (code "72") (name "unconnected-(P1-DB06-Pad15)") (class "Default")
      (node (ref "P1") (pin "15") (pinfunction "DB06_15") (pintype "passive"))
    )
    (net (code "73") (name "unconnected-(P1-DB07-Pad16)") (class "Default")
      (node (ref "P1") (pin "16") (pinfunction "DB07_16") (pintype "passive"))
    )
    (net (code "74") (name "unconnected-(P1-NRST-Pad4)") (class "Default")
      (node (ref "P1") (pin "4") (pinfunction "NRST_4") (pintype "passive"))
    )
    (net (code "75") (name "unconnected-(P1-RD-Pad7)") (class "Default")
      (node (ref "P1") (pin "7") (pinfunction "RD_7") (pintype "passive"))
    )
    (net (code "76") (name "unconnected-(P2-PVDD-Pad5)") (class "Default")
      (node (ref "P2") (pin "5") (pinfunction "PVDD_5") (pintype "passive+no_connect"))
    )
    (net (code "77") (name "unconnected-(P3-IO1-Pad7)") (class "Default")
      (node (ref "P3") (pin "7") (pinfunction "IO1_7") (pintype "passive"))
    )
    (net (code "78") (name "unconnected-(P3-IO2-Pad9)") (class "Default")
      (node (ref "P3") (pin "9") (pinfunction "IO2_9") (pintype "passive"))
    )
    (net (code "79") (name "unconnected-(P3-IO3-Pad14)") (class "Default")
      (node (ref "P3") (pin "14") (pinfunction "IO3_14") (pintype "passive"))
    )
    (net (code "80") (name "unconnected-(P3-IO4-Pad17)") (class "Default")
      (node (ref "P3") (pin "17") (pinfunction "IO4_17") (pintype "passive"))
    )
    (net (code "81") (name "unconnected-(P3-IO7-Pad31)") (class "Default")
      (node (ref "P3") (pin "31") (pinfunction "IO7_31") (pintype "passive"))
    )
    (net (code "82") (name "unconnected-(U1-FB-Pad4)") (class "Default")
      (node (ref "U1") (pin "4") (pinfunction "FB_4") (pintype "input+no_connect"))
    )
  )
)
